# utilidong-test-OR-1_0.net
KiCad netlist of a schematic drawn in EAGLE
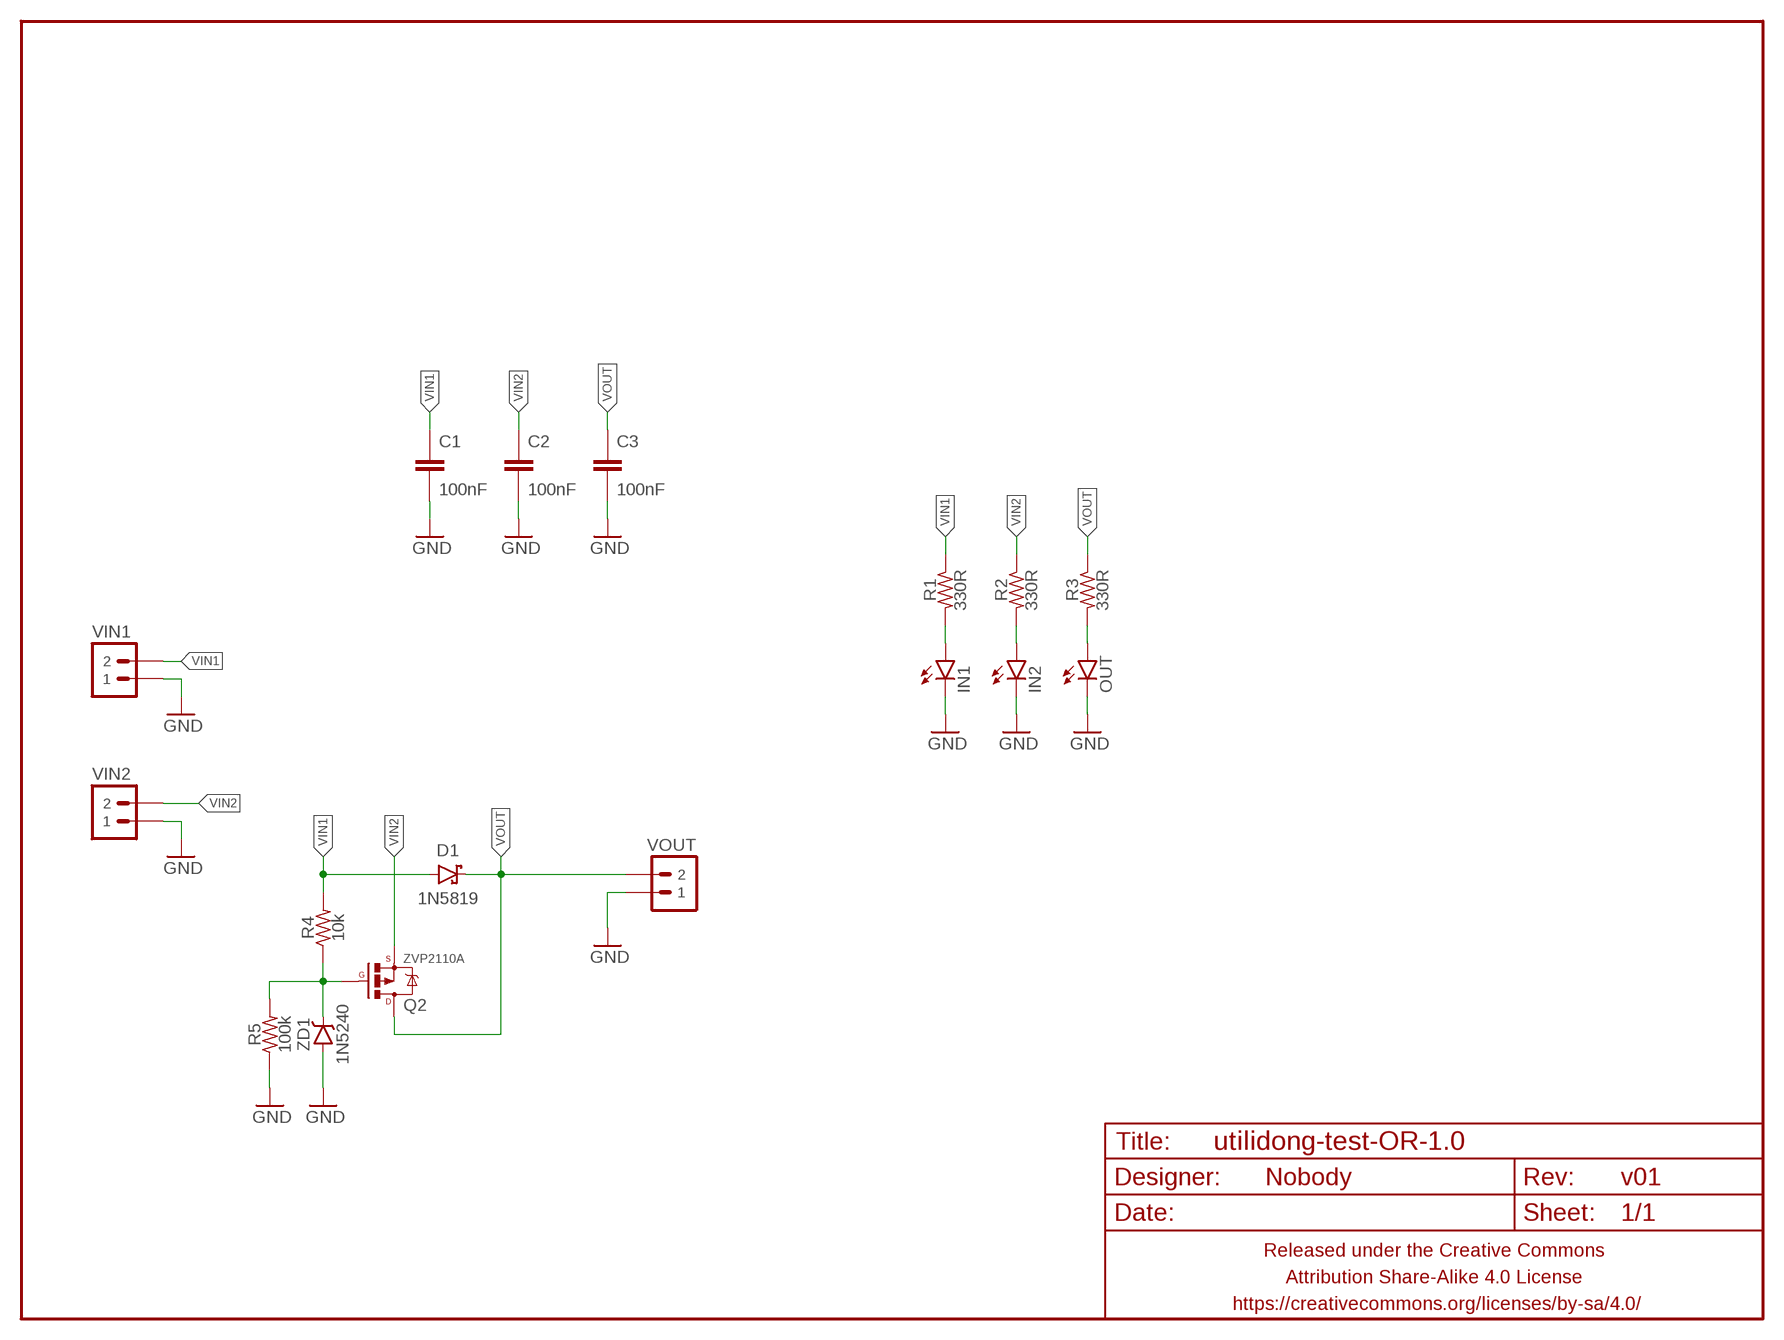
[diagram p0: schematic, sheet 1]

(export (version "E")
  (design (tool "Eeschema 10.0.6"))
  (components
    (comp (ref "C1")
      (value "100nF")
      (footprint "eagle-import:C025-024X044")
      (libsource (lib "eagle-import") (part "CAPACITOR-CERAMIC025-024X044"))
    )
    (comp (ref "C2")
      (value "100nF")
      (footprint "eagle-import:C025-024X044")
      (libsource (lib "eagle-import") (part "CAPACITOR-CERAMIC025-024X044"))
    )
    (comp (ref "C3")
      (value "100nF")
      (footprint "eagle-import:C025-024X044")
      (libsource (lib "eagle-import") (part "CAPACITOR-CERAMIC025-024X044"))
    )
    (comp (ref "D1")
      (value "1N5819")
      (footprint "eagle-import:DIODE-7.62MM")
      (libsource (lib "eagle-import") (part "DIODE-SCHOTTKYPTH-7.62MM"))
    )
    (comp (ref "FRAME1")
      (value "FRAME-LETTERNO_PACKAGE")
      (footprint "eagle-import:DUMMY")
      (fields (field (name "DESIGNER") "Nobody"))
      (libsource (lib "eagle-import") (part "FRAME-LETTERNO_PACKAGE"))
    )
    (comp (ref "IN1")
      (value "LED3MM-LESS")
      (footprint "eagle-import:LED3MM-LESSSILK")
      (libsource (lib "eagle-import") (part "LED3MM-LESS"))
    )
    (comp (ref "IN2")
      (value "LED3MM-LESS")
      (footprint "eagle-import:LED3MM-LESSSILK")
      (libsource (lib "eagle-import") (part "LED3MM-LESS"))
    )
    (comp (ref "OUT")
      (value "LED3MM-LESS")
      (footprint "eagle-import:LED3MM-LESSSILK")
      (libsource (lib "eagle-import") (part "LED3MM-LESS"))
    )
    (comp (ref "Q2")
      (value "ZVP2110A")
      (footprint "eagle-import:TO-92-AMMO")
      (libsource (lib "eagle-import") (part "MOSFET-PCHANNELTO-92-INLINE-DGS"))
    )
    (comp (ref "R1")
      (value "330R")
      (footprint "eagle-import:RESISTOR-AXIAL-PTH-7.62MM")
      (libsource (lib "eagle-import") (part "RESISTORPTH-AXIAL-7.62MM"))
    )
    (comp (ref "R2")
      (value "330R")
      (footprint "eagle-import:RESISTOR-AXIAL-PTH-7.62MM")
      (libsource (lib "eagle-import") (part "RESISTORPTH-AXIAL-7.62MM"))
    )
    (comp (ref "R3")
      (value "330R")
      (footprint "eagle-import:RESISTOR-AXIAL-PTH-7.62MM")
      (libsource (lib "eagle-import") (part "RESISTORPTH-AXIAL-7.62MM"))
    )
    (comp (ref "R4")
      (value "10k")
      (footprint "eagle-import:RESISTOR-AXIAL-PTH-7.62MM")
      (libsource (lib "eagle-import") (part "RESISTORPTH-AXIAL-7.62MM"))
    )
    (comp (ref "R5")
      (value "100k")
      (footprint "eagle-import:RESISTOR-AXIAL-PTH-7.62MM")
      (libsource (lib "eagle-import") (part "RESISTORPTH-AXIAL-7.62MM"))
    )
    (comp (ref "VIN1")
      (value "M02PTH-CENTERED-R+")
      (footprint "eagle-import:1X02-CENTER-R+")
      (libsource (lib "eagle-import") (part "M02PTH-CENTERED-R+"))
    )
    (comp (ref "VIN2")
      (value "M02PTH-CENTERED-R+")
      (footprint "eagle-import:1X02-CENTER-R+")
      (libsource (lib "eagle-import") (part "M02PTH-CENTERED-R+"))
    )
    (comp (ref "VOUT")
      (value "M02PTH-CENTERED-R+")
      (footprint "eagle-import:1X02-CENTER-R+")
      (libsource (lib "eagle-import") (part "M02PTH-CENTERED-R+"))
    )
    (comp (ref "ZD1")
      (value "1N5240")
      (footprint "eagle-import:DIODE-7.62MM")
      (libsource (lib "eagle-import") (part "DIODE-ZENERPTH-7.62MM"))
    )
  )
  (nets
    (net (code "1") (name "GND") (class "Default")
      (node (ref "C1") (pin "2") (pinfunction "2_2") (pintype "passive"))
      (node (ref "C2") (pin "2") (pinfunction "2_2") (pintype "passive"))
      (node (ref "C3") (pin "2") (pinfunction "2_2") (pintype "passive"))
      (node (ref "IN1") (pin "K") (pinfunction "C_K") (pintype "passive"))
      (node (ref "IN2") (pin "K") (pinfunction "C_K") (pintype "passive"))
      (node (ref "OUT") (pin "K") (pinfunction "C_K") (pintype "passive"))
      (node (ref "R5") (pin "P$1") (pinfunction "1_P$1") (pintype "passive"))
      (node (ref "VIN1") (pin "1") (pinfunction "1_1") (pintype "passive"))
      (node (ref "VIN2") (pin "1") (pinfunction "1_1") (pintype "passive"))
      (node (ref "VOUT") (pin "1") (pinfunction "1_1") (pintype "passive"))
      (node (ref "ZD1") (pin "A") (pinfunction "A_A") (pintype "passive"))
    )
    (net (code "2") (name "Net-(Q2-G)") (class "Default")
      (node (ref "Q2") (pin "2") (pinfunction "G_2") (pintype "passive"))
      (node (ref "R4") (pin "P$1") (pinfunction "1_P$1") (pintype "passive"))
      (node (ref "R5") (pin "P$2") (pinfunction "2_P$2") (pintype "passive"))
      (node (ref "ZD1") (pin "K") (pinfunction "C_K") (pintype "passive"))
    )
    (net (code "3") (name "Net-(R1-2)") (class "Default")
      (node (ref "IN1") (pin "A") (pinfunction "A_A") (pintype "passive"))
      (node (ref "R1") (pin "P$2") (pinfunction "2_P$2") (pintype "passive"))
    )
    (net (code "4") (name "Net-(R2-2)") (class "Default")
      (node (ref "IN2") (pin "A") (pinfunction "A_A") (pintype "passive"))
      (node (ref "R2") (pin "P$2") (pinfunction "2_P$2") (pintype "passive"))
    )
    (net (code "5") (name "Net-(R3-2)") (class "Default")
      (node (ref "OUT") (pin "A") (pinfunction "A_A") (pintype "passive"))
      (node (ref "R3") (pin "P$2") (pinfunction "2_P$2") (pintype "passive"))
    )
    (net (code "6") (name "VIN1") (class "Default")
      (node (ref "C1") (pin "1") (pinfunction "1_1") (pintype "passive"))
      (node (ref "D1") (pin "A") (pinfunction "A_A") (pintype "passive"))
      (node (ref "R1") (pin "P$1") (pinfunction "1_P$1") (pintype "passive"))
      (node (ref "R4") (pin "P$2") (pinfunction "2_P$2") (pintype "passive"))
      (node (ref "VIN1") (pin "2") (pinfunction "2_2") (pintype "passive"))
    )
    (net (code "7") (name "VIN2") (class "Default")
      (node (ref "C2") (pin "1") (pinfunction "1_1") (pintype "passive"))
      (node (ref "Q2") (pin "3") (pinfunction "S_3") (pintype "passive"))
      (node (ref "R2") (pin "P$1") (pinfunction "1_P$1") (pintype "passive"))
      (node (ref "VIN2") (pin "2") (pinfunction "2_2") (pintype "passive"))
    )
    (net (code "8") (name "VOUT") (class "Default")
      (node (ref "C3") (pin "1") (pinfunction "1_1") (pintype "passive"))
      (node (ref "D1") (pin "K") (pinfunction "C_K") (pintype "passive"))
      (node (ref "Q2") (pin "1") (pinfunction "D_1") (pintype "passive"))
      (node (ref "R3") (pin "P$1") (pinfunction "1_P$1") (pintype "passive"))
      (node (ref "VOUT") (pin "2") (pinfunction "2_2") (pintype "passive"))
    )
  )
)
